# smartsensorPowered.net
KiCad netlist of a schematic drawn in EAGLE
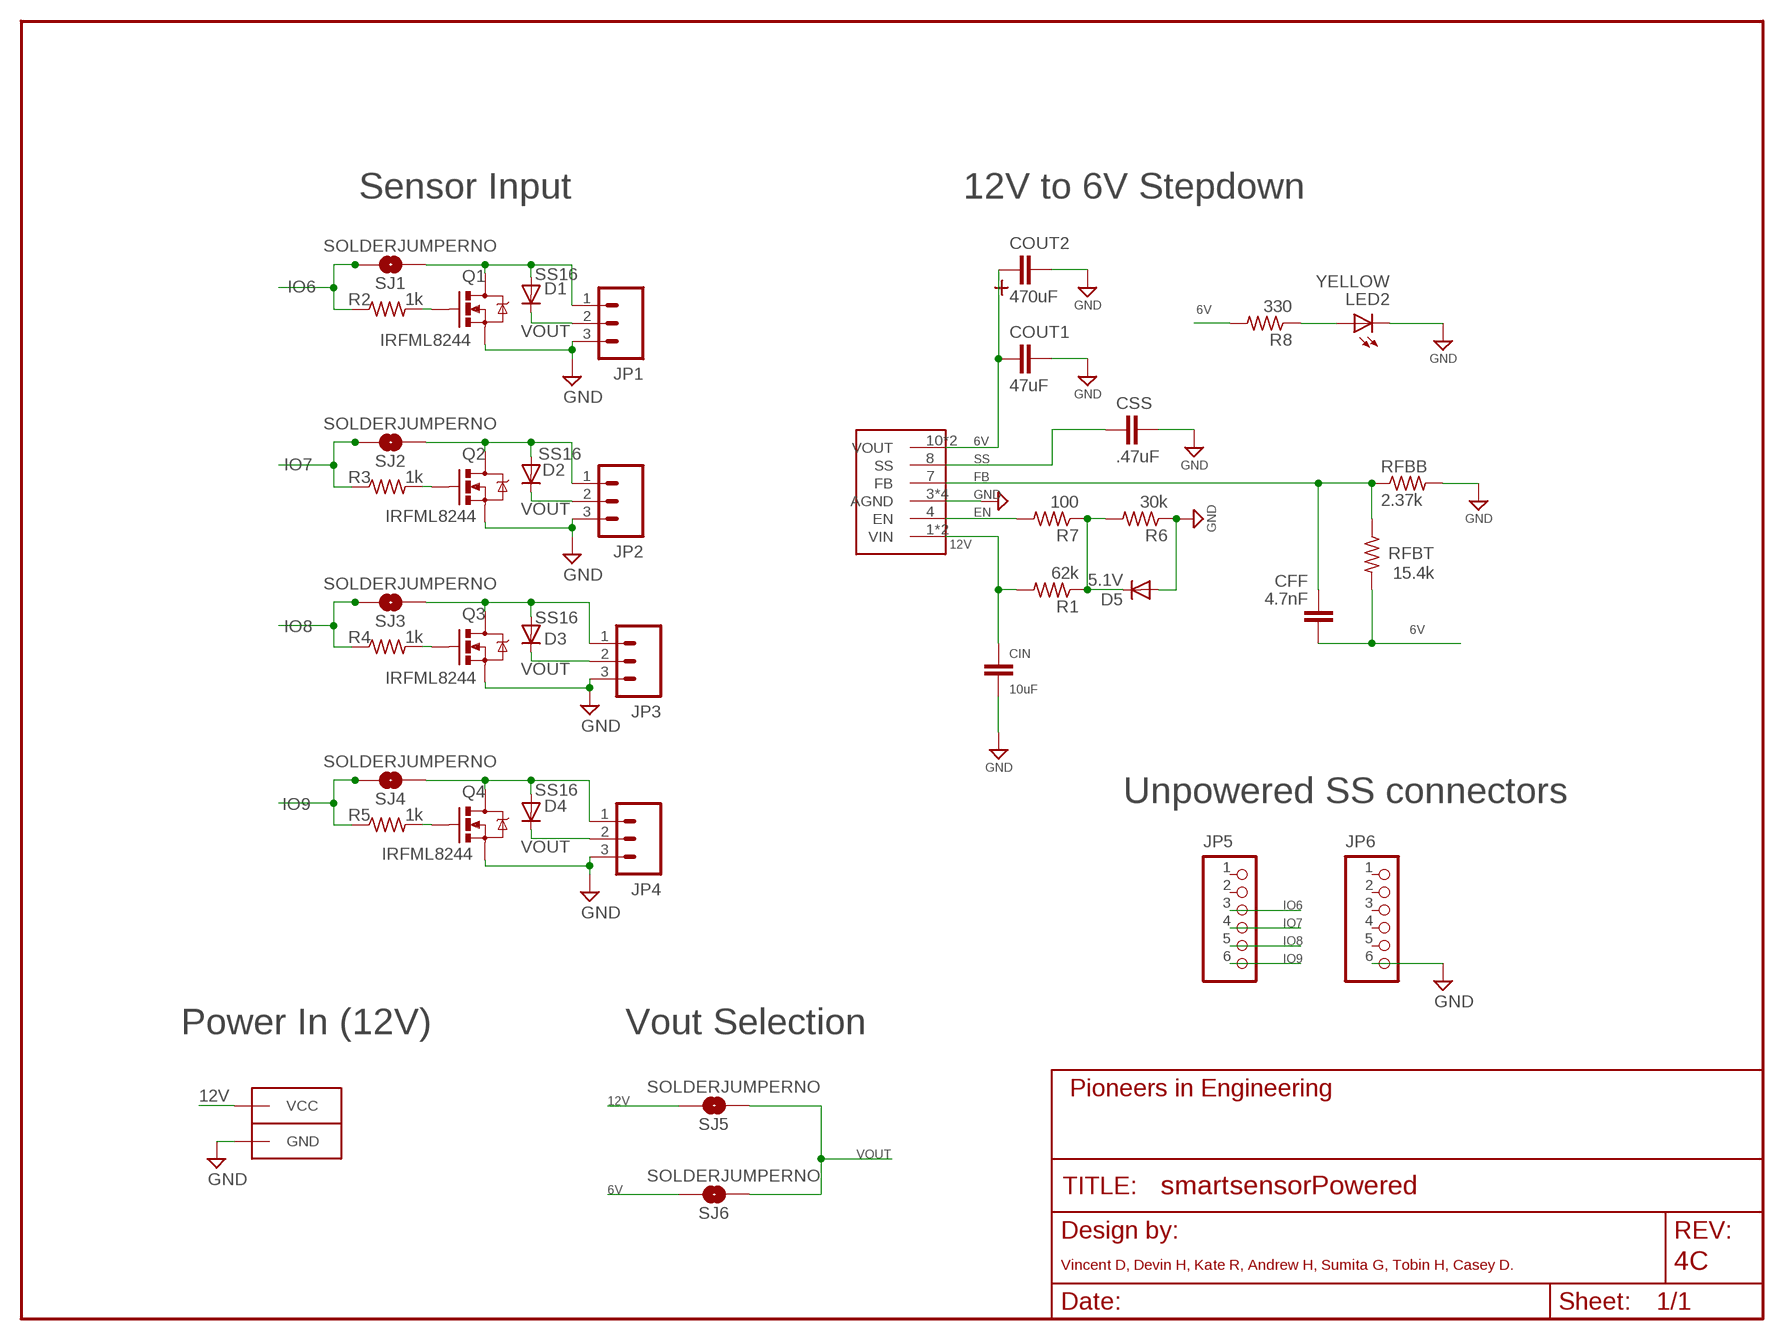
[diagram p0: schematic, sheet 1]

(export (version "E")
  (design (tool "Eeschema 10.0.6"))
  (components
    (comp (ref "CFF")
      (value "4.7nF")
      (footprint "eagle-import:0603-CAP")
      (libsource (lib "eagle-import") (part "CAP0603-CAP"))
    )
    (comp (ref "CIN")
      (value "10uF")
      (footprint "eagle-import:1206")
      (libsource (lib "eagle-import") (part "CAP1206"))
    )
    (comp (ref "CONN1")
      (value "ANDERSONVERTICAL")
      (footprint "eagle-import:ANDERSON_VERTICAL")
      (libsource (lib "eagle-import") (part "ANDERSONVERTICAL"))
    )
    (comp (ref "COUT1")
      (value "47uF")
      (footprint "eagle-import:1206")
      (libsource (lib "eagle-import") (part "CAP1206"))
    )
    (comp (ref "COUT2")
      (value "470uF")
      (footprint "eagle-import:TANT_CASE_E")
      (libsource (lib "eagle-import") (part "TANT_CASE_E"))
    )
    (comp (ref "CSS")
      (value ".47uF")
      (footprint "eagle-import:0603-CAP")
      (libsource (lib "eagle-import") (part "CAP0603-CAP"))
    )
    (comp (ref "D1")
      (value "SS16")
      (footprint "eagle-import:SMA-DIODE_ALT")
      (libsource (lib "eagle-import") (part "DIODESMA-ALT"))
    )
    (comp (ref "D2")
      (value "SS16")
      (footprint "eagle-import:SMA-DIODE_ALT")
      (libsource (lib "eagle-import") (part "DIODESMA-ALT"))
    )
    (comp (ref "D3")
      (value "SS16")
      (footprint "eagle-import:SMA-DIODE_ALT")
      (libsource (lib "eagle-import") (part "DIODESMA-ALT"))
    )
    (comp (ref "D4")
      (value "SS16")
      (footprint "eagle-import:SMA-DIODE_ALT")
      (libsource (lib "eagle-import") (part "DIODESMA-ALT"))
    )
    (comp (ref "D5")
      (value "5.1V")
      (footprint "eagle-import:SOD-323")
      (libsource (lib "eagle-import") (part "DIODESOD-323"))
    )
    (comp (ref "JP1")
      (value "M031X03-MTA")
      (footprint "eagle-import:1X03-MTA")
      (libsource (lib "eagle-import") (part "M031X03-MTA"))
    )
    (comp (ref "JP2")
      (value "M031X03-MTA")
      (footprint "eagle-import:1X03-MTA")
      (libsource (lib "eagle-import") (part "M031X03-MTA"))
    )
    (comp (ref "JP3")
      (value "M031X03-MTA")
      (footprint "eagle-import:1X03-MTA")
      (libsource (lib "eagle-import") (part "M031X03-MTA"))
    )
    (comp (ref "JP4")
      (value "M031X03-MTA")
      (footprint "eagle-import:1X03-MTA")
      (libsource (lib "eagle-import") (part "M031X03-MTA"))
    )
    (comp (ref "JP5")
      (value "PINHD-1X6")
      (footprint "eagle-import:1X06")
      (fields (field (name "PARTNUMBER") "965"))
      (libsource (lib "eagle-import") (part "PINHD-1X6"))
    )
    (comp (ref "JP6")
      (value "PINHD-1X6")
      (footprint "eagle-import:1X06")
      (fields (field (name "PARTNUMBER") "965"))
      (libsource (lib "eagle-import") (part "PINHD-1X6"))
    )
    (comp (ref "LED2")
      (value "YELLOW")
      (footprint "eagle-import:LED-0805")
      (libsource (lib "eagle-import") (part "LED0805"))
    )
    (comp (ref "Q1")
      (value "IRFML8244")
      (footprint "eagle-import:SOT23-3")
      (libsource (lib "eagle-import") (part "MOSFET-NCHANNELSMD"))
    )
    (comp (ref "Q2")
      (value "IRFML8244")
      (footprint "eagle-import:SOT23-3")
      (libsource (lib "eagle-import") (part "MOSFET-NCHANNELSMD"))
    )
    (comp (ref "Q3")
      (value "IRFML8244")
      (footprint "eagle-import:SOT23-3")
      (libsource (lib "eagle-import") (part "MOSFET-NCHANNELSMD"))
    )
    (comp (ref "Q4")
      (value "IRFML8244")
      (footprint "eagle-import:SOT23-3")
      (libsource (lib "eagle-import") (part "MOSFET-NCHANNELSMD"))
    )
    (comp (ref "R1")
      (value "62k")
      (footprint "eagle-import:R0603")
      (libsource (lib "eagle-import") (part "R-US_R0603"))
    )
    (comp (ref "R2")
      (value "1k")
      (footprint "eagle-import:R0603")
      (libsource (lib "eagle-import") (part "R-US_R0603"))
    )
    (comp (ref "R3")
      (value "1k")
      (footprint "eagle-import:R0603")
      (libsource (lib "eagle-import") (part "R-US_R0603"))
    )
    (comp (ref "R4")
      (value "1k")
      (footprint "eagle-import:R0603")
      (libsource (lib "eagle-import") (part "R-US_R0603"))
    )
    (comp (ref "R5")
      (value "1k")
      (footprint "eagle-import:R0603")
      (libsource (lib "eagle-import") (part "R-US_R0603"))
    )
    (comp (ref "R6")
      (value "30k")
      (footprint "eagle-import:R0603")
      (libsource (lib "eagle-import") (part "R-US_R0603"))
    )
    (comp (ref "R7")
      (value "100")
      (footprint "eagle-import:R0603")
      (libsource (lib "eagle-import") (part "R-US_R0603"))
    )
    (comp (ref "R8")
      (value "330")
      (footprint "eagle-import:R0603")
      (libsource (lib "eagle-import") (part "R-US_R0603"))
    )
    (comp (ref "RFBB")
      (value "2.37k")
      (footprint "eagle-import:R0603")
      (libsource (lib "eagle-import") (part "R-US_R0603"))
    )
    (comp (ref "RFBT")
      (value "15.4k")
      (footprint "eagle-import:R0603")
      (libsource (lib "eagle-import") (part "R-US_R0603"))
    )
    (comp (ref "SJ1")
      (value "SOLDERJUMPERNO")
      (footprint "eagle-import:SJ_2S-NO")
      (libsource (lib "eagle-import") (part "SOLDERJUMPERNO"))
    )
    (comp (ref "SJ2")
      (value "SOLDERJUMPERNO")
      (footprint "eagle-import:SJ_2S-NO")
      (libsource (lib "eagle-import") (part "SOLDERJUMPERNO"))
    )
    (comp (ref "SJ3")
      (value "SOLDERJUMPERNO")
      (footprint "eagle-import:SJ_2S-NO")
      (libsource (lib "eagle-import") (part "SOLDERJUMPERNO"))
    )
    (comp (ref "SJ4")
      (value "SOLDERJUMPERNO")
      (footprint "eagle-import:SJ_2S-NO")
      (libsource (lib "eagle-import") (part "SOLDERJUMPERNO"))
    )
    (comp (ref "SJ5")
      (value "SOLDERJUMPERNO")
      (footprint "eagle-import:SJ_2S-NO")
      (libsource (lib "eagle-import") (part "SOLDERJUMPERNO"))
    )
    (comp (ref "SJ6")
      (value "SOLDERJUMPERNO")
      (footprint "eagle-import:SJ_2S-NO")
      (libsource (lib "eagle-import") (part "SOLDERJUMPERNO"))
    )
    (comp (ref "U$3")
      (value "LMZ12010")
      (footprint "eagle-import:LMZ12010")
      (libsource (lib "eagle-import") (part "LMZ12010"))
    )
  )
  (nets
    (net (code "1") (name "/6V") (class "Default")
      (node (ref "CFF") (pin "1") (pinfunction "1_1") (pintype "passive"))
      (node (ref "COUT1") (pin "1") (pinfunction "1_1") (pintype "passive"))
      (node (ref "COUT2") (pin "POS") (pinfunction "POS_POS") (pintype "passive"))
      (node (ref "R8") (pin "2") (pinfunction "2_2") (pintype "passive"))
      (node (ref "RFBT") (pin "2") (pinfunction "2_2") (pintype "passive"))
      (node (ref "SJ6") (pin "1") (pinfunction "1_1") (pintype "passive"))
      (node (ref "U$3") (pin "10") (pinfunction "VOUT_10") (pintype "bidirectional"))
      (node (ref "U$3") (pin "11") (pinfunction "VOUT_11") (pintype "bidirectional"))
    )
    (net (code "2") (name "/12V") (class "Default")
      (node (ref "CIN") (pin "1") (pinfunction "1_1") (pintype "passive"))
      (node (ref "CONN1") (pin "PIN2") (pinfunction "VCC_PIN2") (pintype "bidirectional"))
      (node (ref "R1") (pin "2") (pinfunction "2_2") (pintype "passive"))
      (node (ref "SJ5") (pin "1") (pinfunction "1_1") (pintype "passive"))
      (node (ref "U$3") (pin "1") (pinfunction "VIN_1") (pintype "bidirectional"))
      (node (ref "U$3") (pin "2") (pinfunction "VIN_2") (pintype "bidirectional"))
    )
    (net (code "3") (name "/EN") (class "Default")
      (node (ref "R7") (pin "2") (pinfunction "2_2") (pintype "passive"))
      (node (ref "U$3") (pin "4") (pinfunction "EN_4") (pintype "bidirectional"))
    )
    (net (code "4") (name "/FB") (class "Default")
      (node (ref "CFF") (pin "2") (pinfunction "2_2") (pintype "passive"))
      (node (ref "RFBB") (pin "1") (pinfunction "1_1") (pintype "passive"))
      (node (ref "RFBT") (pin "1") (pinfunction "1_1") (pintype "passive"))
      (node (ref "U$3") (pin "7") (pinfunction "FB_7") (pintype "bidirectional"))
    )
    (net (code "5") (name "/IO6") (class "Default")
      (node (ref "JP5") (pin "3") (pinfunction "3_3") (pintype "passive"))
      (node (ref "R2") (pin "1") (pinfunction "1_1") (pintype "passive"))
      (node (ref "SJ1") (pin "1") (pinfunction "1_1") (pintype "passive"))
    )
    (net (code "6") (name "/IO7") (class "Default")
      (node (ref "JP5") (pin "4") (pinfunction "4_4") (pintype "passive"))
      (node (ref "R3") (pin "1") (pinfunction "1_1") (pintype "passive"))
      (node (ref "SJ2") (pin "1") (pinfunction "1_1") (pintype "passive"))
    )
    (net (code "7") (name "/IO8") (class "Default")
      (node (ref "JP5") (pin "5") (pinfunction "5_5") (pintype "passive"))
      (node (ref "R4") (pin "1") (pinfunction "1_1") (pintype "passive"))
      (node (ref "SJ3") (pin "1") (pinfunction "1_1") (pintype "passive"))
    )
    (net (code "8") (name "/IO9") (class "Default")
      (node (ref "JP5") (pin "6") (pinfunction "6_6") (pintype "passive"))
      (node (ref "R5") (pin "1") (pinfunction "1_1") (pintype "passive"))
      (node (ref "SJ4") (pin "1") (pinfunction "1_1") (pintype "passive"))
    )
    (net (code "9") (name "/SS") (class "Default")
      (node (ref "CSS") (pin "1") (pinfunction "1_1") (pintype "passive"))
      (node (ref "U$3") (pin "8") (pinfunction "SS_8") (pintype "bidirectional"))
    )
    (net (code "10") (name "/VOUT") (class "Default")
      (node (ref "D1") (pin "C") (pinfunction "C_C") (pintype "passive"))
      (node (ref "D2") (pin "C") (pinfunction "C_C") (pintype "passive"))
      (node (ref "D3") (pin "C") (pinfunction "C_C") (pintype "passive"))
      (node (ref "D4") (pin "C") (pinfunction "C_C") (pintype "passive"))
      (node (ref "JP1") (pin "2") (pinfunction "2_2") (pintype "passive"))
      (node (ref "JP2") (pin "2") (pinfunction "2_2") (pintype "passive"))
      (node (ref "JP3") (pin "2") (pinfunction "2_2") (pintype "passive"))
      (node (ref "JP4") (pin "2") (pinfunction "2_2") (pintype "passive"))
      (node (ref "SJ5") (pin "2") (pinfunction "2_2") (pintype "passive"))
      (node (ref "SJ6") (pin "2") (pinfunction "2_2") (pintype "passive"))
    )
    (net (code "11") (name "GND") (class "Default")
      (node (ref "CIN") (pin "2") (pinfunction "2_2") (pintype "passive"))
      (node (ref "CONN1") (pin "PIN1") (pinfunction "GND_PIN1") (pintype "bidirectional"))
      (node (ref "COUT1") (pin "2") (pinfunction "2_2") (pintype "passive"))
      (node (ref "COUT2") (pin "NEG") (pinfunction "NEG_NEG") (pintype "passive"))
      (node (ref "CSS") (pin "2") (pinfunction "2_2") (pintype "passive"))
      (node (ref "D5") (pin "1") (pinfunction "A_1") (pintype "passive"))
      (node (ref "JP1") (pin "3") (pinfunction "3_3") (pintype "passive"))
      (node (ref "JP2") (pin "3") (pinfunction "3_3") (pintype "passive"))
      (node (ref "JP3") (pin "3") (pinfunction "3_3") (pintype "passive"))
      (node (ref "JP4") (pin "3") (pinfunction "3_3") (pintype "passive"))
      (node (ref "JP6") (pin "6") (pinfunction "6_6") (pintype "passive"))
      (node (ref "LED2") (pin "C") (pinfunction "C_C") (pintype "passive"))
      (node (ref "Q1") (pin "2") (pinfunction "S_2") (pintype "passive"))
      (node (ref "Q2") (pin "2") (pinfunction "S_2") (pintype "passive"))
      (node (ref "Q3") (pin "2") (pinfunction "S_2") (pintype "passive"))
      (node (ref "Q4") (pin "2") (pinfunction "S_2") (pintype "passive"))
      (node (ref "R6") (pin "1") (pinfunction "1_1") (pintype "passive"))
      (node (ref "RFBB") (pin "2") (pinfunction "2_2") (pintype "passive"))
      (node (ref "U$3") (pin "3") (pinfunction "AGND_3") (pintype "bidirectional"))
      (node (ref "U$3") (pin "5") (pinfunction "AGND_5") (pintype "bidirectional"))
      (node (ref "U$3") (pin "6") (pinfunction "AGND_6") (pintype "bidirectional"))
      (node (ref "U$3") (pin "GND") (pinfunction "AGND_GND") (pintype "bidirectional"))
    )
    (net (code "12") (name "Net-(D5-C)") (class "Default")
      (node (ref "D5") (pin "2") (pinfunction "C_2") (pintype "passive"))
      (node (ref "R1") (pin "1") (pinfunction "1_1") (pintype "passive"))
      (node (ref "R6") (pin "2") (pinfunction "2_2") (pintype "passive"))
      (node (ref "R7") (pin "1") (pinfunction "1_1") (pintype "passive"))
    )
    (net (code "13") (name "Net-(LED2-PadA)") (class "Default")
      (node (ref "LED2") (pin "A") (pinfunction "A_A") (pintype "passive"))
      (node (ref "R8") (pin "1") (pinfunction "1_1") (pintype "passive"))
    )
    (net (code "14") (name "Net-(Q1-D)") (class "Default")
      (node (ref "D1") (pin "A") (pinfunction "A_A") (pintype "passive"))
      (node (ref "JP1") (pin "1") (pinfunction "1_1") (pintype "passive"))
      (node (ref "Q1") (pin "3") (pinfunction "D_3") (pintype "passive"))
      (node (ref "SJ1") (pin "2") (pinfunction "2_2") (pintype "passive"))
    )
    (net (code "15") (name "Net-(Q1-G)") (class "Default")
      (node (ref "Q1") (pin "1") (pinfunction "G_1") (pintype "passive"))
      (node (ref "R2") (pin "2") (pinfunction "2_2") (pintype "passive"))
    )
    (net (code "16") (name "Net-(Q2-D)") (class "Default")
      (node (ref "D2") (pin "A") (pinfunction "A_A") (pintype "passive"))
      (node (ref "JP2") (pin "1") (pinfunction "1_1") (pintype "passive"))
      (node (ref "Q2") (pin "3") (pinfunction "D_3") (pintype "passive"))
      (node (ref "SJ2") (pin "2") (pinfunction "2_2") (pintype "passive"))
    )
    (net (code "17") (name "Net-(Q2-G)") (class "Default")
      (node (ref "Q2") (pin "1") (pinfunction "G_1") (pintype "passive"))
      (node (ref "R3") (pin "2") (pinfunction "2_2") (pintype "passive"))
    )
    (net (code "18") (name "Net-(Q3-D)") (class "Default")
      (node (ref "D3") (pin "A") (pinfunction "A_A") (pintype "passive"))
      (node (ref "JP3") (pin "1") (pinfunction "1_1") (pintype "passive"))
      (node (ref "Q3") (pin "3") (pinfunction "D_3") (pintype "passive"))
      (node (ref "SJ3") (pin "2") (pinfunction "2_2") (pintype "passive"))
    )
    (net (code "19") (name "Net-(Q3-G)") (class "Default")
      (node (ref "Q3") (pin "1") (pinfunction "G_1") (pintype "passive"))
      (node (ref "R4") (pin "2") (pinfunction "2_2") (pintype "passive"))
    )
    (net (code "20") (name "Net-(Q4-D)") (class "Default")
      (node (ref "D4") (pin "A") (pinfunction "A_A") (pintype "passive"))
      (node (ref "JP4") (pin "1") (pinfunction "1_1") (pintype "passive"))
      (node (ref "Q4") (pin "3") (pinfunction "D_3") (pintype "passive"))
      (node (ref "SJ4") (pin "2") (pinfunction "2_2") (pintype "passive"))
    )
    (net (code "21") (name "Net-(Q4-G)") (class "Default")
      (node (ref "Q4") (pin "1") (pinfunction "G_1") (pintype "passive"))
      (node (ref "R5") (pin "2") (pinfunction "2_2") (pintype "passive"))
    )
    (net (code "22") (name "unconnected-(JP5-Pad1)") (class "Default")
      (node (ref "JP5") (pin "1") (pinfunction "1_1") (pintype "passive"))
    )
    (net (code "23") (name "unconnected-(JP5-Pad2)") (class "Default")
      (node (ref "JP5") (pin "2") (pinfunction "2_2") (pintype "passive"))
    )
    (net (code "24") (name "unconnected-(JP6-Pad1)") (class "Default")
      (node (ref "JP6") (pin "1") (pinfunction "1_1") (pintype "passive"))
    )
    (net (code "25") (name "unconnected-(JP6-Pad2)") (class "Default")
      (node (ref "JP6") (pin "2") (pinfunction "2_2") (pintype "passive"))
    )
    (net (code "26") (name "unconnected-(JP6-Pad3)") (class "Default")
      (node (ref "JP6") (pin "3") (pinfunction "3_3") (pintype "passive"))
    )
    (net (code "27") (name "unconnected-(JP6-Pad4)") (class "Default")
      (node (ref "JP6") (pin "4") (pinfunction "4_4") (pintype "passive"))
    )
    (net (code "28") (name "unconnected-(JP6-Pad5)") (class "Default")
      (node (ref "JP6") (pin "5") (pinfunction "5_5") (pintype "passive"))
    )
  )
)
